# Watchdog.net
KiCad netlist of a schematic drawn in Altium Designer
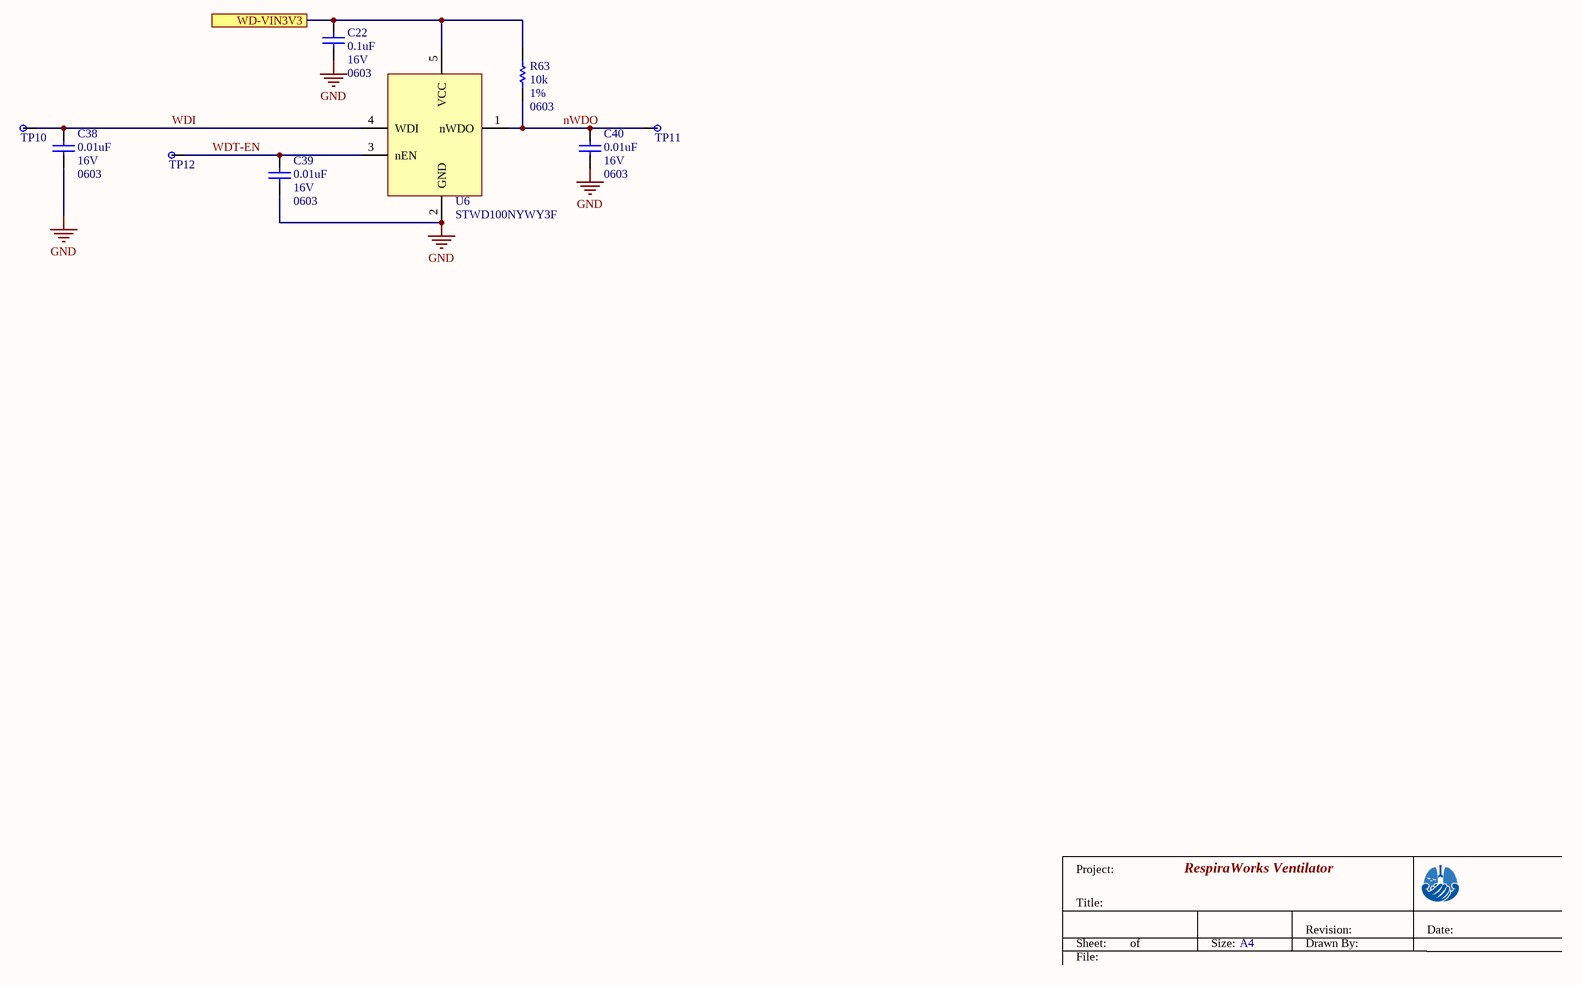
[diagram p0: Watchdog.SchDoc]

(export (version "E")
  (design (tool "Eeschema 10.0.6"))
  (components
    (comp (ref "C22")
      (value "0.1uF")
      (footprint "CAP0603")
      (description "Cap 0603")
      (fields
        (field (name "MANUFACTURER") "Yageo")
        (field (name "VOLTAGE") "16V")
        (field (name "PCB PACKAGE") "0603")
        (field (name "Comment") "CAP 0603")
      )
      (libsource (lib "generic") (part "CAP 0603"))
    )
    (comp (ref "C38")
      (value "0.01uF")
      (footprint "CAP0603")
      (description "Cap 0603")
      (fields
        (field (name "MANUFACTURER") "Samsung")
        (field (name "VOLTAGE") "16V")
        (field (name "PCB PACKAGE") "0603")
        (field (name "Comment") "CAP 0603")
      )
      (libsource (lib "generic") (part "CAP 0603"))
    )
    (comp (ref "C39")
      (value "0.01uF")
      (footprint "CAP0603")
      (description "Cap 0603")
      (fields
        (field (name "MANUFACTURER") "Samsung")
        (field (name "VOLTAGE") "16V")
        (field (name "PCB PACKAGE") "0603")
        (field (name "Comment") "CAP 0603")
      )
      (libsource (lib "generic") (part "CAP 0603"))
    )
    (comp (ref "C40")
      (value "0.01uF")
      (footprint "CAP0603")
      (description "Cap 0603")
      (fields
        (field (name "MANUFACTURER") "Samsung")
        (field (name "VOLTAGE") "16V")
        (field (name "PCB PACKAGE") "0603")
        (field (name "Comment") "CAP 0603")
      )
      (libsource (lib "generic") (part "CAP 0603"))
    )
    (comp (ref "R63")
      (value "10k")
      (footprint "RES0603")
      (description "Res 0603")
      (fields
        (field (name "MANUFACTURER") "Panasonic")
        (field (name "PCB PACKAGE") "0603")
        (field (name "TOLERANCE") "1%")
        (field (name "Comment") "RES 0603")
      )
      (libsource (lib "generic") (part "RES 0603"))
    )
    (comp (ref "TP10")
      (value "TP-SMT")
      (footprint "TP-5015")
      (description "Keystone 5015 SMT Mini Testpoint")
      (fields (field (name "MANUFACTURER") "Keystone") (field (name "TOLERANCE") "5015"))
      (libsource (lib "generic") (part "TP-SMT"))
    )
    (comp (ref "TP11")
      (value "TP-SMT")
      (footprint "TP-5015")
      (description "Keystone 5015 SMT Mini Testpoint")
      (fields (field (name "MANUFACTURER") "Keystone") (field (name "TOLERANCE") "5015"))
      (libsource (lib "generic") (part "TP-SMT"))
    )
    (comp (ref "TP12")
      (value "TP-SMT")
      (footprint "TP-5015")
      (description "Keystone 5015 SMT Mini Testpoint")
      (fields (field (name "MANUFACTURER") "Keystone") (field (name "TOLERANCE") "5015"))
      (libsource (lib "generic") (part "TP-SMT"))
    )
    (comp (ref "U6")
      (value "STWD100NYWY3F")
      (footprint "5-SOT23")
      (description "Watchdog Timer Circuit, 1.6s timeout")
      (fields (field (name "MANUFACTURER") "ST"))
      (libsource (lib "st") (part "STWD100NYWY3F"))
    )
  )
  (nets
    (net (code "1") (name "/WD-VIN3V3") (class "Default")
      (node (ref "C22") (pin "1") (pinfunction "1_1") (pintype "passive"))
      (node (ref "R63") (pin "2") (pinfunction "2_2") (pintype "passive"))
      (node (ref "U6") (pin "5") (pinfunction "VCC_5") (pintype "passive"))
    )
    (net (code "2") (name "/WDI") (class "Default")
      (node (ref "C38") (pin "1") (pinfunction "1_1") (pintype "passive"))
      (node (ref "TP10") (pin "1") (pinfunction "1_1") (pintype "passive"))
      (node (ref "U6") (pin "4") (pinfunction "WDI_4") (pintype "passive"))
    )
    (net (code "3") (name "/WDT-EN") (class "Default")
      (node (ref "C39") (pin "1") (pinfunction "1_1") (pintype "passive"))
      (node (ref "TP12") (pin "1") (pinfunction "1_1") (pintype "passive"))
      (node (ref "U6") (pin "3") (pinfunction "nEN_3") (pintype "passive"))
    )
    (net (code "4") (name "/nWDO") (class "Default")
      (node (ref "C40") (pin "1") (pinfunction "1_1") (pintype "passive"))
      (node (ref "R63") (pin "1") (pinfunction "1_1") (pintype "passive"))
      (node (ref "TP11") (pin "1") (pinfunction "1_1") (pintype "passive"))
      (node (ref "U6") (pin "1") (pinfunction "nWDO_1") (pintype "passive"))
    )
    (net (code "5") (name "GND") (class "Default")
      (node (ref "C22") (pin "2") (pinfunction "2_2") (pintype "passive"))
      (node (ref "C38") (pin "2") (pinfunction "2_2") (pintype "passive"))
      (node (ref "C39") (pin "2") (pinfunction "2_2") (pintype "passive"))
      (node (ref "C40") (pin "2") (pinfunction "2_2") (pintype "passive"))
      (node (ref "U6") (pin "2") (pinfunction "GND_2") (pintype "passive"))
    )
  )
)
